# switch_matrix.net
KiCad netlist of a schematic drawn in Altium Designer
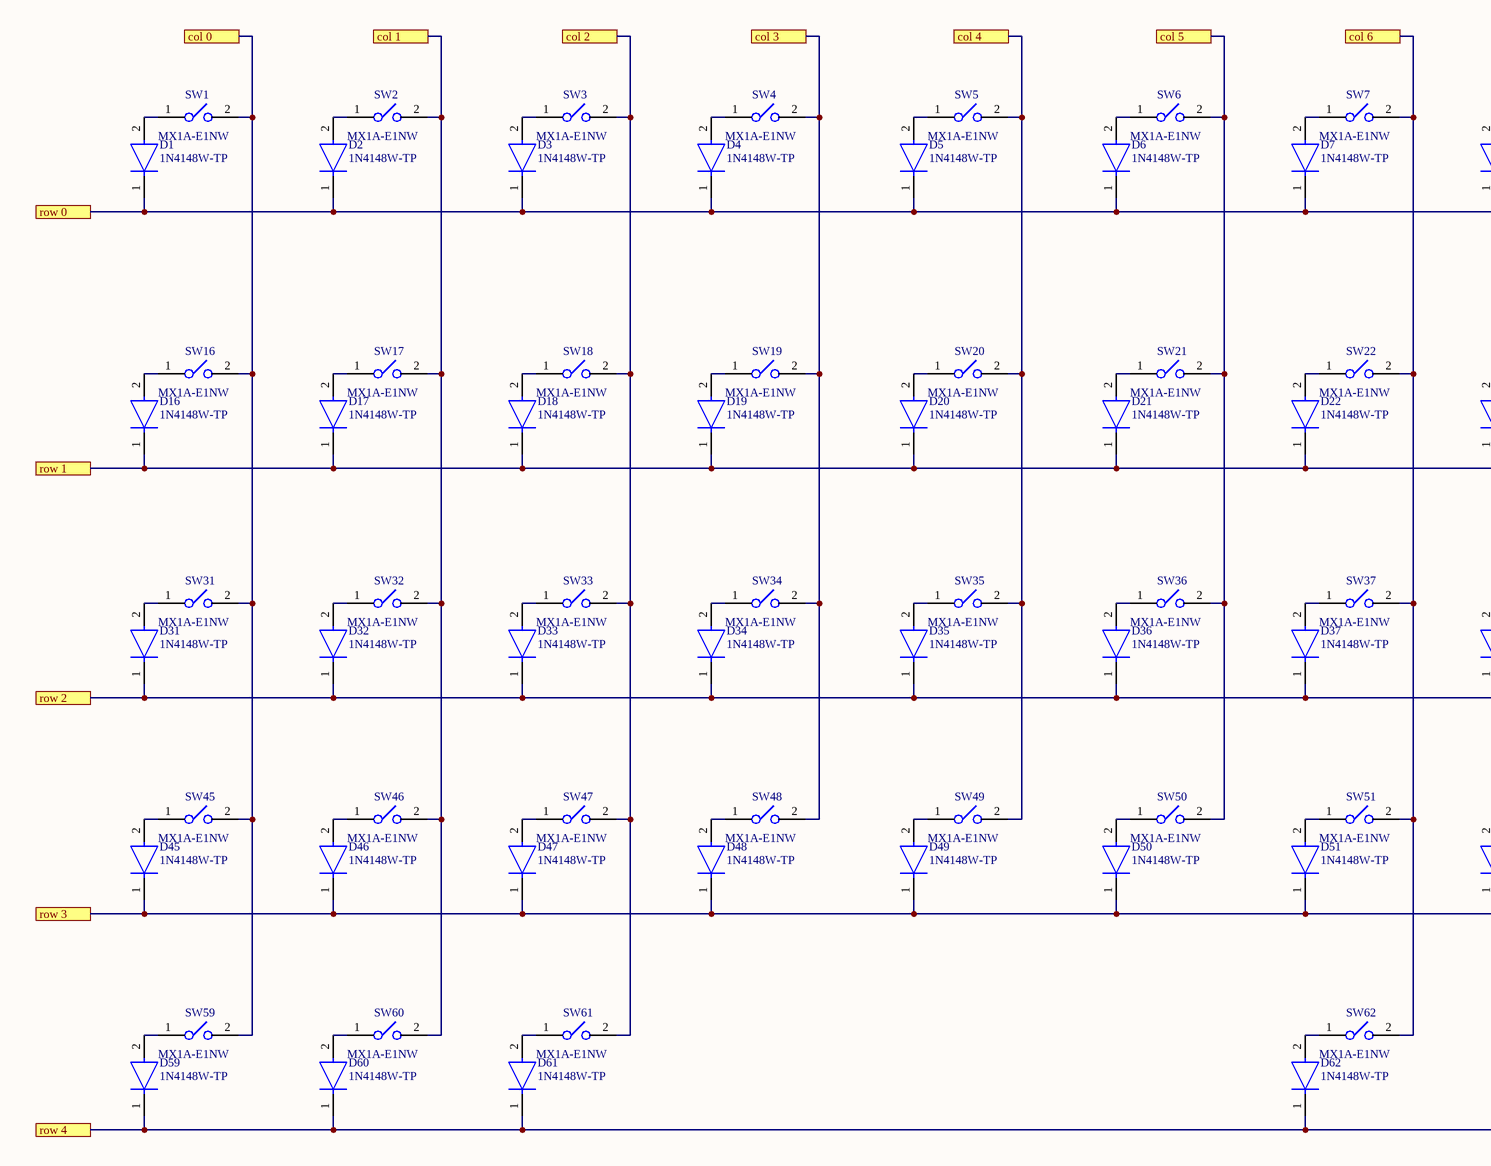
[diagram p0: switch matrix.SchDoc, left]
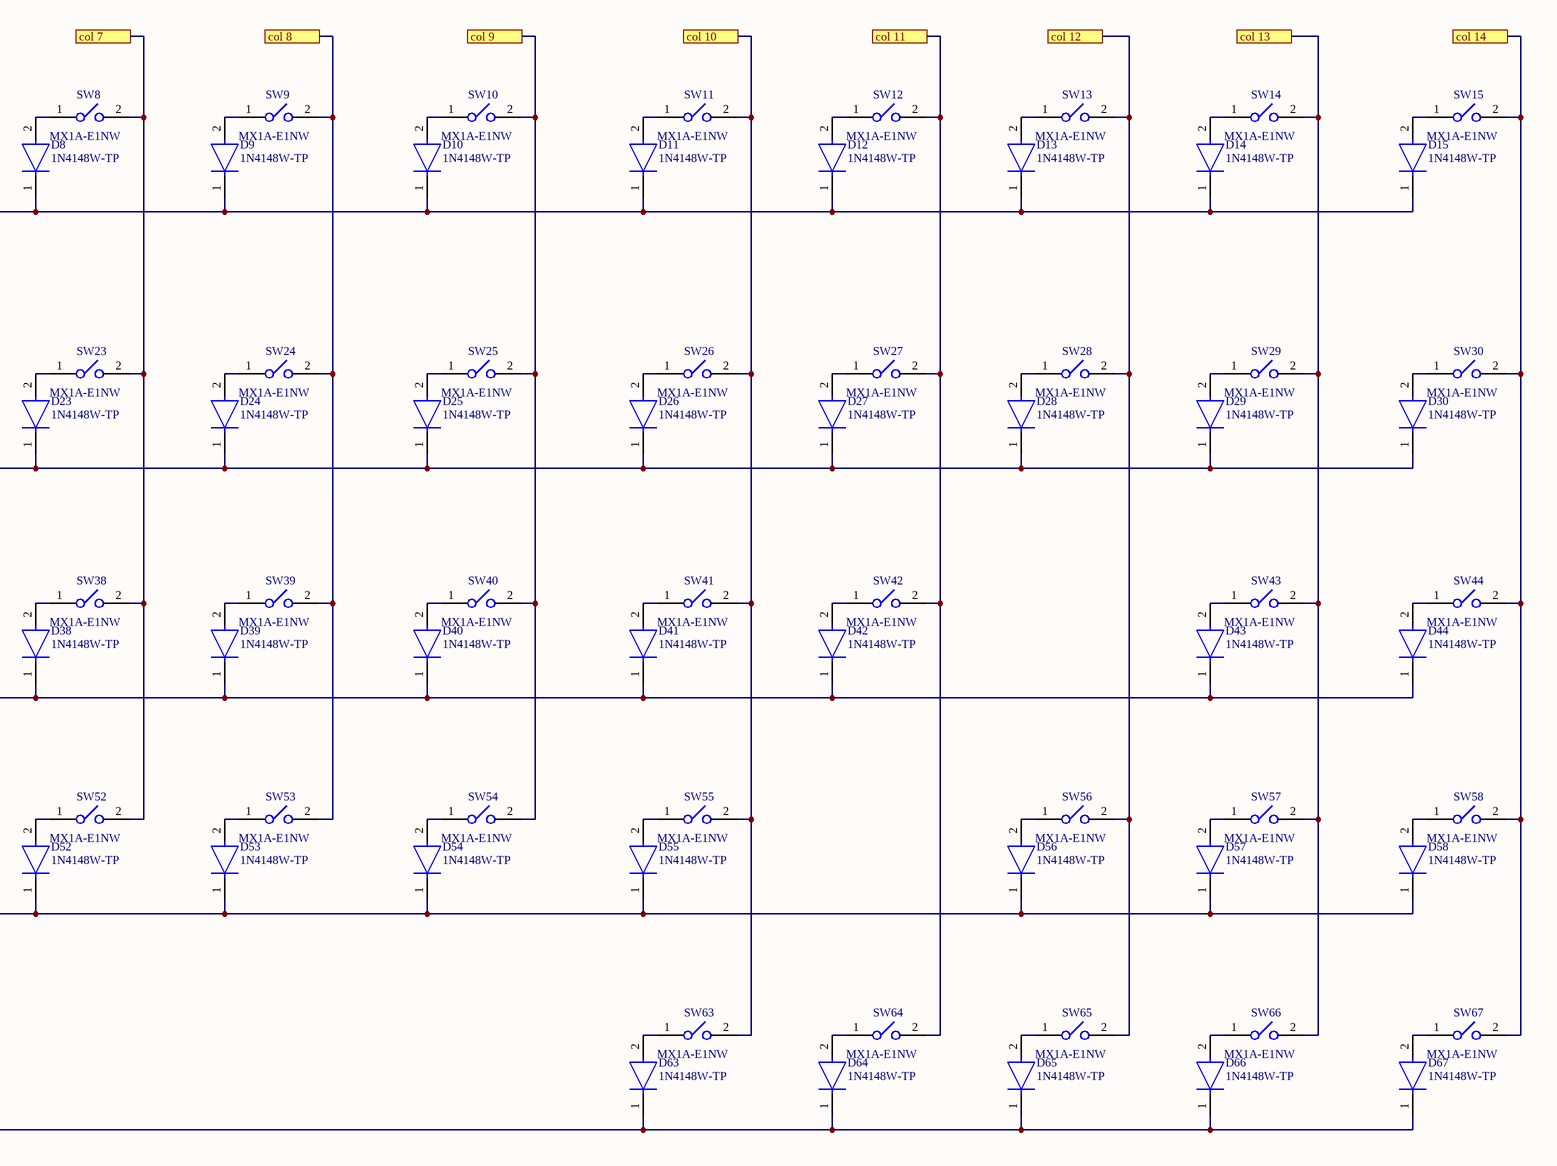
[diagram p1: switch matrix.SchDoc, right]

(export (version "E")
  (design (tool "Eeschema 10.0.6"))
  (components
    (comp (ref "D1")
      (value "1N4148W-TP")
      (footprint "FP-SOD-123-IPC_A")
      (description "DIODE GEN PURP 100V 150MA SOD123")
      (libsource (lib "Altium Content Vault") (part "d7152d700b627762746794eb795d46e"))
    )
    (comp (ref "D2")
      (value "1N4148W-TP")
      (footprint "FP-SOD-123-IPC_A")
      (description "DIODE GEN PURP 100V 150MA SOD123")
      (libsource (lib "Altium Content Vault") (part "d7152d700b627762746794eb795d46e"))
    )
    (comp (ref "D3")
      (value "1N4148W-TP")
      (footprint "FP-SOD-123-IPC_A")
      (description "DIODE GEN PURP 100V 150MA SOD123")
      (libsource (lib "Altium Content Vault") (part "d7152d700b627762746794eb795d46e"))
    )
    (comp (ref "D4")
      (value "1N4148W-TP")
      (footprint "FP-SOD-123-IPC_A")
      (description "DIODE GEN PURP 100V 150MA SOD123")
      (libsource (lib "Altium Content Vault") (part "d7152d700b627762746794eb795d46e"))
    )
    (comp (ref "D5")
      (value "1N4148W-TP")
      (footprint "FP-SOD-123-IPC_A")
      (description "DIODE GEN PURP 100V 150MA SOD123")
      (libsource (lib "Altium Content Vault") (part "d7152d700b627762746794eb795d46e"))
    )
    (comp (ref "D6")
      (value "1N4148W-TP")
      (footprint "FP-SOD-123-IPC_A")
      (description "DIODE GEN PURP 100V 150MA SOD123")
      (libsource (lib "Altium Content Vault") (part "d7152d700b627762746794eb795d46e"))
    )
    (comp (ref "D7")
      (value "1N4148W-TP")
      (footprint "FP-SOD-123-IPC_A")
      (description "DIODE GEN PURP 100V 150MA SOD123")
      (libsource (lib "Altium Content Vault") (part "d7152d700b627762746794eb795d46e"))
    )
    (comp (ref "D8")
      (value "1N4148W-TP")
      (footprint "FP-SOD-123-IPC_A")
      (description "DIODE GEN PURP 100V 150MA SOD123")
      (libsource (lib "Altium Content Vault") (part "d7152d700b627762746794eb795d46e"))
    )
    (comp (ref "D9")
      (value "1N4148W-TP")
      (footprint "FP-SOD-123-IPC_A")
      (description "DIODE GEN PURP 100V 150MA SOD123")
      (libsource (lib "Altium Content Vault") (part "d7152d700b627762746794eb795d46e"))
    )
    (comp (ref "D10")
      (value "1N4148W-TP")
      (footprint "FP-SOD-123-IPC_A")
      (description "DIODE GEN PURP 100V 150MA SOD123")
      (libsource (lib "Altium Content Vault") (part "d7152d700b627762746794eb795d46e"))
    )
    (comp (ref "D11")
      (value "1N4148W-TP")
      (footprint "FP-SOD-123-IPC_A")
      (description "DIODE GEN PURP 100V 150MA SOD123")
      (libsource (lib "Altium Content Vault") (part "d7152d700b627762746794eb795d46e"))
    )
    (comp (ref "D12")
      (value "1N4148W-TP")
      (footprint "FP-SOD-123-IPC_A")
      (description "DIODE GEN PURP 100V 150MA SOD123")
      (libsource (lib "Altium Content Vault") (part "d7152d700b627762746794eb795d46e"))
    )
    (comp (ref "D13")
      (value "1N4148W-TP")
      (footprint "FP-SOD-123-IPC_A")
      (description "DIODE GEN PURP 100V 150MA SOD123")
      (libsource (lib "Altium Content Vault") (part "d7152d700b627762746794eb795d46e"))
    )
    (comp (ref "D14")
      (value "1N4148W-TP")
      (footprint "FP-SOD-123-IPC_A")
      (description "DIODE GEN PURP 100V 150MA SOD123")
      (libsource (lib "Altium Content Vault") (part "d7152d700b627762746794eb795d46e"))
    )
    (comp (ref "D15")
      (value "1N4148W-TP")
      (footprint "FP-SOD-123-IPC_A")
      (description "DIODE GEN PURP 100V 150MA SOD123")
      (libsource (lib "Altium Content Vault") (part "d7152d700b627762746794eb795d46e"))
    )
    (comp (ref "D16")
      (value "1N4148W-TP")
      (footprint "FP-SOD-123-IPC_A")
      (description "DIODE GEN PURP 100V 150MA SOD123")
      (libsource (lib "Altium Content Vault") (part "d7152d700b627762746794eb795d46e"))
    )
    (comp (ref "D17")
      (value "1N4148W-TP")
      (footprint "FP-SOD-123-IPC_A")
      (description "DIODE GEN PURP 100V 150MA SOD123")
      (libsource (lib "Altium Content Vault") (part "d7152d700b627762746794eb795d46e"))
    )
    (comp (ref "D18")
      (value "1N4148W-TP")
      (footprint "FP-SOD-123-IPC_A")
      (description "DIODE GEN PURP 100V 150MA SOD123")
      (libsource (lib "Altium Content Vault") (part "d7152d700b627762746794eb795d46e"))
    )
    (comp (ref "D19")
      (value "1N4148W-TP")
      (footprint "FP-SOD-123-IPC_A")
      (description "DIODE GEN PURP 100V 150MA SOD123")
      (libsource (lib "Altium Content Vault") (part "d7152d700b627762746794eb795d46e"))
    )
    (comp (ref "D20")
      (value "1N4148W-TP")
      (footprint "FP-SOD-123-IPC_A")
      (description "DIODE GEN PURP 100V 150MA SOD123")
      (libsource (lib "Altium Content Vault") (part "d7152d700b627762746794eb795d46e"))
    )
    (comp (ref "D21")
      (value "1N4148W-TP")
      (footprint "FP-SOD-123-IPC_A")
      (description "DIODE GEN PURP 100V 150MA SOD123")
      (libsource (lib "Altium Content Vault") (part "d7152d700b627762746794eb795d46e"))
    )
    (comp (ref "D22")
      (value "1N4148W-TP")
      (footprint "FP-SOD-123-IPC_A")
      (description "DIODE GEN PURP 100V 150MA SOD123")
      (libsource (lib "Altium Content Vault") (part "d7152d700b627762746794eb795d46e"))
    )
    (comp (ref "D23")
      (value "1N4148W-TP")
      (footprint "FP-SOD-123-IPC_A")
      (description "DIODE GEN PURP 100V 150MA SOD123")
      (libsource (lib "Altium Content Vault") (part "d7152d700b627762746794eb795d46e"))
    )
    (comp (ref "D24")
      (value "1N4148W-TP")
      (footprint "FP-SOD-123-IPC_A")
      (description "DIODE GEN PURP 100V 150MA SOD123")
      (libsource (lib "Altium Content Vault") (part "d7152d700b627762746794eb795d46e"))
    )
    (comp (ref "D25")
      (value "1N4148W-TP")
      (footprint "FP-SOD-123-IPC_A")
      (description "DIODE GEN PURP 100V 150MA SOD123")
      (libsource (lib "Altium Content Vault") (part "d7152d700b627762746794eb795d46e"))
    )
    (comp (ref "D26")
      (value "1N4148W-TP")
      (footprint "FP-SOD-123-IPC_A")
      (description "DIODE GEN PURP 100V 150MA SOD123")
      (libsource (lib "Altium Content Vault") (part "d7152d700b627762746794eb795d46e"))
    )
    (comp (ref "D27")
      (value "1N4148W-TP")
      (footprint "FP-SOD-123-IPC_A")
      (description "DIODE GEN PURP 100V 150MA SOD123")
      (libsource (lib "Altium Content Vault") (part "d7152d700b627762746794eb795d46e"))
    )
    (comp (ref "D28")
      (value "1N4148W-TP")
      (footprint "FP-SOD-123-IPC_A")
      (description "DIODE GEN PURP 100V 150MA SOD123")
      (libsource (lib "Altium Content Vault") (part "d7152d700b627762746794eb795d46e"))
    )
    (comp (ref "D29")
      (value "1N4148W-TP")
      (footprint "FP-SOD-123-IPC_A")
      (description "DIODE GEN PURP 100V 150MA SOD123")
      (libsource (lib "Altium Content Vault") (part "d7152d700b627762746794eb795d46e"))
    )
    (comp (ref "D30")
      (value "1N4148W-TP")
      (footprint "FP-SOD-123-IPC_A")
      (description "DIODE GEN PURP 100V 150MA SOD123")
      (libsource (lib "Altium Content Vault") (part "d7152d700b627762746794eb795d46e"))
    )
    (comp (ref "D31")
      (value "1N4148W-TP")
      (footprint "FP-SOD-123-IPC_A")
      (description "DIODE GEN PURP 100V 150MA SOD123")
      (libsource (lib "Altium Content Vault") (part "d7152d700b627762746794eb795d46e"))
    )
    (comp (ref "D32")
      (value "1N4148W-TP")
      (footprint "FP-SOD-123-IPC_A")
      (description "DIODE GEN PURP 100V 150MA SOD123")
      (libsource (lib "Altium Content Vault") (part "d7152d700b627762746794eb795d46e"))
    )
    (comp (ref "D33")
      (value "1N4148W-TP")
      (footprint "FP-SOD-123-IPC_A")
      (description "DIODE GEN PURP 100V 150MA SOD123")
      (libsource (lib "Altium Content Vault") (part "d7152d700b627762746794eb795d46e"))
    )
    (comp (ref "D34")
      (value "1N4148W-TP")
      (footprint "FP-SOD-123-IPC_A")
      (description "DIODE GEN PURP 100V 150MA SOD123")
      (libsource (lib "Altium Content Vault") (part "d7152d700b627762746794eb795d46e"))
    )
    (comp (ref "D35")
      (value "1N4148W-TP")
      (footprint "FP-SOD-123-IPC_A")
      (description "DIODE GEN PURP 100V 150MA SOD123")
      (libsource (lib "Altium Content Vault") (part "d7152d700b627762746794eb795d46e"))
    )
    (comp (ref "D36")
      (value "1N4148W-TP")
      (footprint "FP-SOD-123-IPC_A")
      (description "DIODE GEN PURP 100V 150MA SOD123")
      (libsource (lib "Altium Content Vault") (part "d7152d700b627762746794eb795d46e"))
    )
    (comp (ref "D37")
      (value "1N4148W-TP")
      (footprint "FP-SOD-123-IPC_A")
      (description "DIODE GEN PURP 100V 150MA SOD123")
      (libsource (lib "Altium Content Vault") (part "d7152d700b627762746794eb795d46e"))
    )
    (comp (ref "D38")
      (value "1N4148W-TP")
      (footprint "FP-SOD-123-IPC_A")
      (description "DIODE GEN PURP 100V 150MA SOD123")
      (libsource (lib "Altium Content Vault") (part "d7152d700b627762746794eb795d46e"))
    )
    (comp (ref "D39")
      (value "1N4148W-TP")
      (footprint "FP-SOD-123-IPC_A")
      (description "DIODE GEN PURP 100V 150MA SOD123")
      (libsource (lib "Altium Content Vault") (part "d7152d700b627762746794eb795d46e"))
    )
    (comp (ref "D40")
      (value "1N4148W-TP")
      (footprint "FP-SOD-123-IPC_A")
      (description "DIODE GEN PURP 100V 150MA SOD123")
      (libsource (lib "Altium Content Vault") (part "d7152d700b627762746794eb795d46e"))
    )
    (comp (ref "D41")
      (value "1N4148W-TP")
      (footprint "FP-SOD-123-IPC_A")
      (description "DIODE GEN PURP 100V 150MA SOD123")
      (libsource (lib "Altium Content Vault") (part "d7152d700b627762746794eb795d46e"))
    )
    (comp (ref "D42")
      (value "1N4148W-TP")
      (footprint "FP-SOD-123-IPC_A")
      (description "DIODE GEN PURP 100V 150MA SOD123")
      (libsource (lib "Altium Content Vault") (part "d7152d700b627762746794eb795d46e"))
    )
    (comp (ref "D43")
      (value "1N4148W-TP")
      (footprint "FP-SOD-123-IPC_A")
      (description "DIODE GEN PURP 100V 150MA SOD123")
      (libsource (lib "Altium Content Vault") (part "d7152d700b627762746794eb795d46e"))
    )
    (comp (ref "D44")
      (value "1N4148W-TP")
      (footprint "FP-SOD-123-IPC_A")
      (description "DIODE GEN PURP 100V 150MA SOD123")
      (libsource (lib "Altium Content Vault") (part "d7152d700b627762746794eb795d46e"))
    )
    (comp (ref "D45")
      (value "1N4148W-TP")
      (footprint "FP-SOD-123-IPC_A")
      (description "DIODE GEN PURP 100V 150MA SOD123")
      (libsource (lib "Altium Content Vault") (part "d7152d700b627762746794eb795d46e"))
    )
    (comp (ref "D46")
      (value "1N4148W-TP")
      (footprint "FP-SOD-123-IPC_A")
      (description "DIODE GEN PURP 100V 150MA SOD123")
      (libsource (lib "Altium Content Vault") (part "d7152d700b627762746794eb795d46e"))
    )
    (comp (ref "D47")
      (value "1N4148W-TP")
      (footprint "FP-SOD-123-IPC_A")
      (description "DIODE GEN PURP 100V 150MA SOD123")
      (libsource (lib "Altium Content Vault") (part "d7152d700b627762746794eb795d46e"))
    )
    (comp (ref "D48")
      (value "1N4148W-TP")
      (footprint "FP-SOD-123-IPC_A")
      (description "DIODE GEN PURP 100V 150MA SOD123")
      (libsource (lib "Altium Content Vault") (part "d7152d700b627762746794eb795d46e"))
    )
    (comp (ref "D49")
      (value "1N4148W-TP")
      (footprint "FP-SOD-123-IPC_A")
      (description "DIODE GEN PURP 100V 150MA SOD123")
      (libsource (lib "Altium Content Vault") (part "d7152d700b627762746794eb795d46e"))
    )
    (comp (ref "D50")
      (value "1N4148W-TP")
      (footprint "FP-SOD-123-IPC_A")
      (description "DIODE GEN PURP 100V 150MA SOD123")
      (libsource (lib "Altium Content Vault") (part "d7152d700b627762746794eb795d46e"))
    )
    (comp (ref "D51")
      (value "1N4148W-TP")
      (footprint "FP-SOD-123-IPC_A")
      (description "DIODE GEN PURP 100V 150MA SOD123")
      (libsource (lib "Altium Content Vault") (part "d7152d700b627762746794eb795d46e"))
    )
    (comp (ref "D52")
      (value "1N4148W-TP")
      (footprint "FP-SOD-123-IPC_A")
      (description "DIODE GEN PURP 100V 150MA SOD123")
      (libsource (lib "Altium Content Vault") (part "d7152d700b627762746794eb795d46e"))
    )
    (comp (ref "D53")
      (value "1N4148W-TP")
      (footprint "FP-SOD-123-IPC_A")
      (description "DIODE GEN PURP 100V 150MA SOD123")
      (libsource (lib "Altium Content Vault") (part "d7152d700b627762746794eb795d46e"))
    )
    (comp (ref "D54")
      (value "1N4148W-TP")
      (footprint "FP-SOD-123-IPC_A")
      (description "DIODE GEN PURP 100V 150MA SOD123")
      (libsource (lib "Altium Content Vault") (part "d7152d700b627762746794eb795d46e"))
    )
    (comp (ref "D55")
      (value "1N4148W-TP")
      (footprint "FP-SOD-123-IPC_A")
      (description "DIODE GEN PURP 100V 150MA SOD123")
      (libsource (lib "Altium Content Vault") (part "d7152d700b627762746794eb795d46e"))
    )
    (comp (ref "D56")
      (value "1N4148W-TP")
      (footprint "FP-SOD-123-IPC_A")
      (description "DIODE GEN PURP 100V 150MA SOD123")
      (libsource (lib "Altium Content Vault") (part "d7152d700b627762746794eb795d46e"))
    )
    (comp (ref "D57")
      (value "1N4148W-TP")
      (footprint "FP-SOD-123-IPC_A")
      (description "DIODE GEN PURP 100V 150MA SOD123")
      (libsource (lib "Altium Content Vault") (part "d7152d700b627762746794eb795d46e"))
    )
    (comp (ref "D58")
      (value "1N4148W-TP")
      (footprint "FP-SOD-123-IPC_A")
      (description "DIODE GEN PURP 100V 150MA SOD123")
      (libsource (lib "Altium Content Vault") (part "d7152d700b627762746794eb795d46e"))
    )
    (comp (ref "D59")
      (value "1N4148W-TP")
      (footprint "FP-SOD-123-IPC_A")
      (description "DIODE GEN PURP 100V 150MA SOD123")
      (libsource (lib "Altium Content Vault") (part "d7152d700b627762746794eb795d46e"))
    )
    (comp (ref "D60")
      (value "1N4148W-TP")
      (footprint "FP-SOD-123-IPC_A")
      (description "DIODE GEN PURP 100V 150MA SOD123")
      (libsource (lib "Altium Content Vault") (part "d7152d700b627762746794eb795d46e"))
    )
    (comp (ref "D61")
      (value "1N4148W-TP")
      (footprint "FP-SOD-123-IPC_A")
      (description "DIODE GEN PURP 100V 150MA SOD123")
      (libsource (lib "Altium Content Vault") (part "d7152d700b627762746794eb795d46e"))
    )
    (comp (ref "D62")
      (value "1N4148W-TP")
      (footprint "FP-SOD-123-IPC_A")
      (description "DIODE GEN PURP 100V 150MA SOD123")
      (libsource (lib "Altium Content Vault") (part "d7152d700b627762746794eb795d46e"))
    )
    (comp (ref "D63")
      (value "1N4148W-TP")
      (footprint "FP-SOD-123-IPC_A")
      (description "DIODE GEN PURP 100V 150MA SOD123")
      (libsource (lib "Altium Content Vault") (part "d7152d700b627762746794eb795d46e"))
    )
    (comp (ref "D64")
      (value "1N4148W-TP")
      (footprint "FP-SOD-123-IPC_A")
      (description "DIODE GEN PURP 100V 150MA SOD123")
      (libsource (lib "Altium Content Vault") (part "d7152d700b627762746794eb795d46e"))
    )
    (comp (ref "D65")
      (value "1N4148W-TP")
      (footprint "FP-SOD-123-IPC_A")
      (description "DIODE GEN PURP 100V 150MA SOD123")
      (libsource (lib "Altium Content Vault") (part "d7152d700b627762746794eb795d46e"))
    )
    (comp (ref "D66")
      (value "1N4148W-TP")
      (footprint "FP-SOD-123-IPC_A")
      (description "DIODE GEN PURP 100V 150MA SOD123")
      (libsource (lib "Altium Content Vault") (part "d7152d700b627762746794eb795d46e"))
    )
    (comp (ref "D67")
      (value "1N4148W-TP")
      (footprint "FP-SOD-123-IPC_A")
      (description "DIODE GEN PURP 100V 150MA SOD123")
      (libsource (lib "Altium Content Vault") (part "d7152d700b627762746794eb795d46e"))
    )
    (comp (ref "SW1")
      (value "Switch_Key_Switch_MX1A-E1NW_eec")
      (footprint "SW_Cherry_MX_1.00u_PCB")
      (description "SWITCH PUSH SPST-NO 0.01A 12V")
      (fields
        (field (name "PART NUMBER") "MX1A-E1NW")
        (field (name "VOLTAGE") "12V")
        (field (name "MANUFACTURER") "Key Switch")
      )
      (libsource (lib "Switch_Key_Switch_MX1A-E1NW_eec") (part "Switch_Key_Switch_MX1A-E1NW_eec"))
    )
    (comp (ref "SW2")
      (value "Switch_Key_Switch_MX1A-E1NW_eec")
      (footprint "SW_Cherry_MX_1.00u_PCB")
      (description "SWITCH PUSH SPST-NO 0.01A 12V")
      (fields
        (field (name "PART NUMBER") "MX1A-E1NW")
        (field (name "VOLTAGE") "12V")
        (field (name "MANUFACTURER") "Key Switch")
      )
      (libsource (lib "Switch_Key_Switch_MX1A-E1NW_eec") (part "Switch_Key_Switch_MX1A-E1NW_eec"))
    )
    (comp (ref "SW3")
      (value "Switch_Key_Switch_MX1A-E1NW_eec")
      (footprint "SW_Cherry_MX_1.00u_PCB")
      (description "SWITCH PUSH SPST-NO 0.01A 12V")
      (fields
        (field (name "PART NUMBER") "MX1A-E1NW")
        (field (name "VOLTAGE") "12V")
        (field (name "MANUFACTURER") "Key Switch")
      )
      (libsource (lib "Switch_Key_Switch_MX1A-E1NW_eec") (part "Switch_Key_Switch_MX1A-E1NW_eec"))
    )
    (comp (ref "SW4")
      (value "Switch_Key_Switch_MX1A-E1NW_eec")
      (footprint "SW_Cherry_MX_1.00u_PCB")
      (description "SWITCH PUSH SPST-NO 0.01A 12V")
      (fields
        (field (name "PART NUMBER") "MX1A-E1NW")
        (field (name "VOLTAGE") "12V")
        (field (name "MANUFACTURER") "Key Switch")
      )
      (libsource (lib "Switch_Key_Switch_MX1A-E1NW_eec") (part "Switch_Key_Switch_MX1A-E1NW_eec"))
    )
    (comp (ref "SW5")
      (value "Switch_Key_Switch_MX1A-E1NW_eec")
      (footprint "SW_Cherry_MX_1.00u_PCB")
      (description "SWITCH PUSH SPST-NO 0.01A 12V")
      (fields
        (field (name "PART NUMBER") "MX1A-E1NW")
        (field (name "VOLTAGE") "12V")
        (field (name "MANUFACTURER") "Key Switch")
      )
      (libsource (lib "Switch_Key_Switch_MX1A-E1NW_eec") (part "Switch_Key_Switch_MX1A-E1NW_eec"))
    )
    (comp (ref "SW6")
      (value "Switch_Key_Switch_MX1A-E1NW_eec")
      (footprint "SW_Cherry_MX_1.00u_PCB")
      (description "SWITCH PUSH SPST-NO 0.01A 12V")
      (fields
        (field (name "PART NUMBER") "MX1A-E1NW")
        (field (name "VOLTAGE") "12V")
        (field (name "MANUFACTURER") "Key Switch")
      )
      (libsource (lib "Switch_Key_Switch_MX1A-E1NW_eec") (part "Switch_Key_Switch_MX1A-E1NW_eec"))
    )
    (comp (ref "SW7")
      (value "Switch_Key_Switch_MX1A-E1NW_eec")
      (footprint "SW_Cherry_MX_1.00u_PCB")
      (description "SWITCH PUSH SPST-NO 0.01A 12V")
      (fields
        (field (name "PART NUMBER") "MX1A-E1NW")
        (field (name "VOLTAGE") "12V")
        (field (name "MANUFACTURER") "Key Switch")
      )
      (libsource (lib "Switch_Key_Switch_MX1A-E1NW_eec") (part "Switch_Key_Switch_MX1A-E1NW_eec"))
    )
    (comp (ref "SW8")
      (value "Switch_Key_Switch_MX1A-E1NW_eec")
      (footprint "SW_Cherry_MX_1.00u_PCB")
      (description "SWITCH PUSH SPST-NO 0.01A 12V")
      (fields
        (field (name "PART NUMBER") "MX1A-E1NW")
        (field (name "VOLTAGE") "12V")
        (field (name "MANUFACTURER") "Key Switch")
      )
      (libsource (lib "Switch_Key_Switch_MX1A-E1NW_eec") (part "Switch_Key_Switch_MX1A-E1NW_eec"))
    )
    (comp (ref "SW9")
      (value "Switch_Key_Switch_MX1A-E1NW_eec")
      (footprint "SW_Cherry_MX_1.00u_PCB")
      (description "SWITCH PUSH SPST-NO 0.01A 12V")
      (fields
        (field (name "PART NUMBER") "MX1A-E1NW")
        (field (name "VOLTAGE") "12V")
        (field (name "MANUFACTURER") "Key Switch")
      )
      (libsource (lib "Switch_Key_Switch_MX1A-E1NW_eec") (part "Switch_Key_Switch_MX1A-E1NW_eec"))
    )
    (comp (ref "SW10")
      (value "Switch_Key_Switch_MX1A-E1NW_eec")
      (footprint "SW_Cherry_MX_1.00u_PCB")
      (description "SWITCH PUSH SPST-NO 0.01A 12V")
      (fields
        (field (name "PART NUMBER") "MX1A-E1NW")
        (field (name "VOLTAGE") "12V")
        (field (name "MANUFACTURER") "Key Switch")
      )
      (libsource (lib "Switch_Key_Switch_MX1A-E1NW_eec") (part "Switch_Key_Switch_MX1A-E1NW_eec"))
    )
    (comp (ref "SW11")
      (value "Switch_Key_Switch_MX1A-E1NW_eec")
      (footprint "SW_Cherry_MX_1.00u_PCB")
      (description "SWITCH PUSH SPST-NO 0.01A 12V")
      (fields
        (field (name "PART NUMBER") "MX1A-E1NW")
        (field (name "VOLTAGE") "12V")
        (field (name "MANUFACTURER") "Key Switch")
      )
      (libsource (lib "Switch_Key_Switch_MX1A-E1NW_eec") (part "Switch_Key_Switch_MX1A-E1NW_eec"))
    )
    (comp (ref "SW12")
      (value "Switch_Key_Switch_MX1A-E1NW_eec")
      (footprint "SW_Cherry_MX_1.00u_PCB")
      (description "SWITCH PUSH SPST-NO 0.01A 12V")
      (fields
        (field (name "PART NUMBER") "MX1A-E1NW")
        (field (name "VOLTAGE") "12V")
        (field (name "MANUFACTURER") "Key Switch")
      )
      (libsource (lib "Switch_Key_Switch_MX1A-E1NW_eec") (part "Switch_Key_Switch_MX1A-E1NW_eec"))
    )
    (comp (ref "SW13")
      (value "Switch_Key_Switch_MX1A-E1NW_eec")
      (footprint "SW_Cherry_MX_1.00u_PCB")
      (description "SWITCH PUSH SPST-NO 0.01A 12V")
      (fields
        (field (name "PART NUMBER") "MX1A-E1NW")
        (field (name "VOLTAGE") "12V")
        (field (name "MANUFACTURER") "Key Switch")
      )
      (libsource (lib "Switch_Key_Switch_MX1A-E1NW_eec") (part "Switch_Key_Switch_MX1A-E1NW_eec"))
    )
    (comp (ref "SW14")
      (value "Switch_Key_Switch_MX1A-E1NW_eec")
      (footprint "SW_Cherry_MX_2.00u_PCB")
      (description "SWITCH PUSH SPST-NO 0.01A 12V")
      (fields
        (field (name "PART NUMBER") "MX1A-E1NW")
        (field (name "VOLTAGE") "12V")
        (field (name "MANUFACTURER") "Key Switch")
      )
      (libsource (lib "Switch_Key_Switch_MX1A-E1NW_eec") (part "Switch_Key_Switch_MX1A-E1NW_eec"))
    )
    (comp (ref "SW15")
      (value "Switch_Key_Switch_MX1A-E1NW_eec")
      (footprint "SW_Cherry_MX_1.00u_PCB")
      (description "SWITCH PUSH SPST-NO 0.01A 12V")
      (fields
        (field (name "PART NUMBER") "MX1A-E1NW")
        (field (name "VOLTAGE") "12V")
        (field (name "MANUFACTURER") "Key Switch")
      )
      (libsource (lib "Switch_Key_Switch_MX1A-E1NW_eec") (part "Switch_Key_Switch_MX1A-E1NW_eec"))
    )
    (comp (ref "SW16")
      (value "Switch_Key_Switch_MX1A-E1NW_eec")
      (footprint "SW_Cherry_MX_1.50u_PCB")
      (description "SWITCH PUSH SPST-NO 0.01A 12V")
      (fields
        (field (name "PART NUMBER") "MX1A-E1NW")
        (field (name "VOLTAGE") "12V")
        (field (name "MANUFACTURER") "Key Switch")
      )
      (libsource (lib "Switch_Key_Switch_MX1A-E1NW_eec") (part "Switch_Key_Switch_MX1A-E1NW_eec"))
    )
    (comp (ref "SW17")
      (value "Switch_Key_Switch_MX1A-E1NW_eec")
      (footprint "SW_Cherry_MX_1.00u_PCB")
      (description "SWITCH PUSH SPST-NO 0.01A 12V")
      (fields
        (field (name "PART NUMBER") "MX1A-E1NW")
        (field (name "VOLTAGE") "12V")
        (field (name "MANUFACTURER") "Key Switch")
      )
      (libsource (lib "Switch_Key_Switch_MX1A-E1NW_eec") (part "Switch_Key_Switch_MX1A-E1NW_eec"))
    )
    (comp (ref "SW18")
      (value "Switch_Key_Switch_MX1A-E1NW_eec")
      (footprint "SW_Cherry_MX_1.00u_PCB")
      (description "SWITCH PUSH SPST-NO 0.01A 12V")
      (fields
        (field (name "PART NUMBER") "MX1A-E1NW")
        (field (name "VOLTAGE") "12V")
        (field (name "MANUFACTURER") "Key Switch")
      )
      (libsource (lib "Switch_Key_Switch_MX1A-E1NW_eec") (part "Switch_Key_Switch_MX1A-E1NW_eec"))
    )
    (comp (ref "SW19")
      (value "Switch_Key_Switch_MX1A-E1NW_eec")
      (footprint "SW_Cherry_MX_1.00u_PCB")
      (description "SWITCH PUSH SPST-NO 0.01A 12V")
      (fields
        (field (name "PART NUMBER") "MX1A-E1NW")
        (field (name "VOLTAGE") "12V")
        (field (name "MANUFACTURER") "Key Switch")
      )
      (libsource (lib "Switch_Key_Switch_MX1A-E1NW_eec") (part "Switch_Key_Switch_MX1A-E1NW_eec"))
    )
    (comp (ref "SW20")
      (value "Switch_Key_Switch_MX1A-E1NW_eec")
      (footprint "SW_Cherry_MX_1.00u_PCB")
      (description "SWITCH PUSH SPST-NO 0.01A 12V")
      (fields
        (field (name "PART NUMBER") "MX1A-E1NW")
        (field (name "VOLTAGE") "12V")
        (field (name "MANUFACTURER") "Key Switch")
      )
      (libsource (lib "Switch_Key_Switch_MX1A-E1NW_eec") (part "Switch_Key_Switch_MX1A-E1NW_eec"))
    )
    (comp (ref "SW21")
      (value "Switch_Key_Switch_MX1A-E1NW_eec")
      (footprint "SW_Cherry_MX_1.00u_PCB")
      (description "SWITCH PUSH SPST-NO 0.01A 12V")
      (fields
        (field (name "PART NUMBER") "MX1A-E1NW")
        (field (name "VOLTAGE") "12V")
        (field (name "MANUFACTURER") "Key Switch")
      )
      (libsource (lib "Switch_Key_Switch_MX1A-E1NW_eec") (part "Switch_Key_Switch_MX1A-E1NW_eec"))
    )
    (comp (ref "SW22")
      (value "Switch_Key_Switch_MX1A-E1NW_eec")
      (footprint "SW_Cherry_MX_1.00u_PCB")
      (description "SWITCH PUSH SPST-NO 0.01A 12V")
      (fields
        (field (name "PART NUMBER") "MX1A-E1NW")
        (field (name "VOLTAGE") "12V")
        (field (name "MANUFACTURER") "Key Switch")
      )
      (libsource (lib "Switch_Key_Switch_MX1A-E1NW_eec") (part "Switch_Key_Switch_MX1A-E1NW_eec"))
    )
    (comp (ref "SW23")
      (value "Switch_Key_Switch_MX1A-E1NW_eec")
      (footprint "SW_Cherry_MX_1.00u_PCB")
      (description "SWITCH PUSH SPST-NO 0.01A 12V")
      (fields
        (field (name "PART NUMBER") "MX1A-E1NW")
        (field (name "VOLTAGE") "12V")
        (field (name "MANUFACTURER") "Key Switch")
      )
      (libsource (lib "Switch_Key_Switch_MX1A-E1NW_eec") (part "Switch_Key_Switch_MX1A-E1NW_eec"))
    )
    (comp (ref "SW24")
      (value "Switch_Key_Switch_MX1A-E1NW_eec")
      (footprint "SW_Cherry_MX_1.00u_PCB")
      (description "SWITCH PUSH SPST-NO 0.01A 12V")
      (fields
        (field (name "PART NUMBER") "MX1A-E1NW")
        (field (name "VOLTAGE") "12V")
        (field (name "MANUFACTURER") "Key Switch")
      )
      (libsource (lib "Switch_Key_Switch_MX1A-E1NW_eec") (part "Switch_Key_Switch_MX1A-E1NW_eec"))
    )
    (comp (ref "SW25")
      (value "Switch_Key_Switch_MX1A-E1NW_eec")
      (footprint "SW_Cherry_MX_1.00u_PCB")
      (description "SWITCH PUSH SPST-NO 0.01A 12V")
      (fields
        (field (name "PART NUMBER") "MX1A-E1NW")
        (field (name "VOLTAGE") "12V")
        (field (name "MANUFACTURER") "Key Switch")
      )
      (libsource (lib "Switch_Key_Switch_MX1A-E1NW_eec") (part "Switch_Key_Switch_MX1A-E1NW_eec"))
    )
    (comp (ref "SW26")
      (value "Switch_Key_Switch_MX1A-E1NW_eec")
      (footprint "SW_Cherry_MX_1.00u_PCB")
      (description "SWITCH PUSH SPST-NO 0.01A 12V")
      (fields
        (field (name "PART NUMBER") "MX1A-E1NW")
        (field (name "VOLTAGE") "12V")
        (field (name "MANUFACTURER") "Key Switch")
      )
      (libsource (lib "Switch_Key_Switch_MX1A-E1NW_eec") (part "Switch_Key_Switch_MX1A-E1NW_eec"))
    )
    (comp (ref "SW27")
      (value "Switch_Key_Switch_MX1A-E1NW_eec")
      (footprint "SW_Cherry_MX_1.00u_PCB")
      (description "SWITCH PUSH SPST-NO 0.01A 12V")
      (fields
        (field (name "PART NUMBER") "MX1A-E1NW")
        (field (name "VOLTAGE") "12V")
        (field (name "MANUFACTURER") "Key Switch")
      )
      (libsource (lib "Switch_Key_Switch_MX1A-E1NW_eec") (part "Switch_Key_Switch_MX1A-E1NW_eec"))
    )
    (comp (ref "SW28")
      (value "Switch_Key_Switch_MX1A-E1NW_eec")
      (footprint "SW_Cherry_MX_1.00u_PCB")
      (description "SWITCH PUSH SPST-NO 0.01A 12V")
      (fields
        (field (name "PART NUMBER") "MX1A-E1NW")
        (field (name "VOLTAGE") "12V")
        (field (name "MANUFACTURER") "Key Switch")
      )
      (libsource (lib "Switch_Key_Switch_MX1A-E1NW_eec") (part "Switch_Key_Switch_MX1A-E1NW_eec"))
    )
    (comp (ref "SW29")
      (value "Switch_Key_Switch_MX1A-E1NW_eec")
      (footprint "SW_Cherry_MX_1.50u_PCB")
      (description "SWITCH PUSH SPST-NO 0.01A 12V")
      (fields
        (field (name "PART NUMBER") "MX1A-E1NW")
        (field (name "VOLTAGE") "12V")
        (field (name "MANUFACTURER") "Key Switch")
      )
      (libsource (lib "Switch_Key_Switch_MX1A-E1NW_eec") (part "Switch_Key_Switch_MX1A-E1NW_eec"))
    )
    (comp (ref "SW30")
      (value "Switch_Key_Switch_MX1A-E1NW_eec")
      (footprint "SW_Cherry_MX_1.00u_PCB")
      (description "SWITCH PUSH SPST-NO 0.01A 12V")
      (fields
        (field (name "PART NUMBER") "MX1A-E1NW")
        (field (name "VOLTAGE") "12V")
        (field (name "MANUFACTURER") "Key Switch")
      )
      (libsource (lib "Switch_Key_Switch_MX1A-E1NW_eec") (part "Switch_Key_Switch_MX1A-E1NW_eec"))
    )
    (comp (ref "SW31")
      (value "Switch_Key_Switch_MX1A-E1NW_eec")
      (footprint "SW_Cherry_MX_1.75u_PCB")
      (description "SWITCH PUSH SPST-NO 0.01A 12V")
      (fields
        (field (name "PART NUMBER") "MX1A-E1NW")
        (field (name "VOLTAGE") "12V")
        (field (name "MANUFACTURER") "Key Switch")
      )
      (libsource (lib "Switch_Key_Switch_MX1A-E1NW_eec") (part "Switch_Key_Switch_MX1A-E1NW_eec"))
    )
    (comp (ref "SW32")
      (value "Switch_Key_Switch_MX1A-E1NW_eec")
      (footprint "SW_Cherry_MX_1.00u_PCB")
      (description "SWITCH PUSH SPST-NO 0.01A 12V")
      (fields
        (field (name "PART NUMBER") "MX1A-E1NW")
        (field (name "VOLTAGE") "12V")
        (field (name "MANUFACTURER") "Key Switch")
      )
      (libsource (lib "Switch_Key_Switch_MX1A-E1NW_eec") (part "Switch_Key_Switch_MX1A-E1NW_eec"))
    )
    (comp (ref "SW33")
      (value "Switch_Key_Switch_MX1A-E1NW_eec")
      (footprint "SW_Cherry_MX_1.00u_PCB")
      (description "SWITCH PUSH SPST-NO 0.01A 12V")
      (fields
        (field (name "PART NUMBER") "MX1A-E1NW")
        (field (name "VOLTAGE") "12V")
        (field (name "MANUFACTURER") "Key Switch")
      )
      (libsource (lib "Switch_Key_Switch_MX1A-E1NW_eec") (part "Switch_Key_Switch_MX1A-E1NW_eec"))
    )
    (comp (ref "SW34")
      (value "Switch_Key_Switch_MX1A-E1NW_eec")
      (footprint "SW_Cherry_MX_1.00u_PCB")
      (description "SWITCH PUSH SPST-NO 0.01A 12V")
      (fields
        (field (name "PART NUMBER") "MX1A-E1NW")
        (field (name "VOLTAGE") "12V")
        (field (name "MANUFACTURER") "Key Switch")
      )
      (libsource (lib "Switch_Key_Switch_MX1A-E1NW_eec") (part "Switch_Key_Switch_MX1A-E1NW_eec"))
    )
    (comp (ref "SW35")
      (value "Switch_Key_Switch_MX1A-E1NW_eec")
      (footprint "SW_Cherry_MX_1.00u_PCB")
      (description "SWITCH PUSH SPST-NO 0.01A 12V")
      (fields
        (field (name "PART NUMBER") "MX1A-E1NW")
        (field (name "VOLTAGE") "12V")
        (field (name "MANUFACTURER") "Key Switch")
      )
      (libsource (lib "Switch_Key_Switch_MX1A-E1NW_eec") (part "Switch_Key_Switch_MX1A-E1NW_eec"))
    )
    (comp (ref "SW36")
      (value "Switch_Key_Switch_MX1A-E1NW_eec")
      (footprint "SW_Cherry_MX_1.00u_PCB")
      (description "SWITCH PUSH SPST-NO 0.01A 12V")
      (fields
        (field (name "PART NUMBER") "MX1A-E1NW")
        (field (name "VOLTAGE") "12V")
        (field (name "MANUFACTURER") "Key Switch")
      )
      (libsource (lib "Switch_Key_Switch_MX1A-E1NW_eec") (part "Switch_Key_Switch_MX1A-E1NW_eec"))
    )
    (comp (ref "SW37")
      (value "Switch_Key_Switch_MX1A-E1NW_eec")
      (footprint "SW_Cherry_MX_1.00u_PCB")
      (description "SWITCH PUSH SPST-NO 0.01A 12V")
      (fields
        (field (name "PART NUMBER") "MX1A-E1NW")
        (field (name "VOLTAGE") "12V")
        (field (name "MANUFACTURER") "Key Switch")
      )
      (libsource (lib "Switch_Key_Switch_MX1A-E1NW_eec") (part "Switch_Key_Switch_MX1A-E1NW_eec"))
    )
    (comp (ref "SW38")
      (value "Switch_Key_Switch_MX1A-E1NW_eec")
      (footprint "SW_Cherry_MX_1.00u_PCB")
      (description "SWITCH PUSH SPST-NO 0.01A 12V")
      (fields
        (field (name "PART NUMBER") "MX1A-E1NW")
        (field (name "VOLTAGE") "12V")
        (field (name "MANUFACTURER") "Key Switch")
      )
      (libsource (lib "Switch_Key_Switch_MX1A-E1NW_eec") (part "Switch_Key_Switch_MX1A-E1NW_eec"))
    )
    (comp (ref "SW39")
      (value "Switch_Key_Switch_MX1A-E1NW_eec")
      (footprint "SW_Cherry_MX_1.00u_PCB")
      (description "SWITCH PUSH SPST-NO 0.01A 12V")
      (fields
        (field (name "PART NUMBER") "MX1A-E1NW")
        (field (name "VOLTAGE") "12V")
        (field (name "MANUFACTURER") "Key Switch")
      )
      (libsource (lib "Switch_Key_Switch_MX1A-E1NW_eec") (part "Switch_Key_Switch_MX1A-E1NW_eec"))
    )
    (comp (ref "SW40")
      (value "Switch_Key_Switch_MX1A-E1NW_eec")
      (footprint "SW_Cherry_MX_1.00u_PCB")
      (description "SWITCH PUSH SPST-NO 0.01A 12V")
      (fields
        (field (name "PART NUMBER") "MX1A-E1NW")
        (field (name "VOLTAGE") "12V")
        (field (name "MANUFACTURER") "Key Switch")
      )
      (libsource (lib "Switch_Key_Switch_MX1A-E1NW_eec") (part "Switch_Key_Switch_MX1A-E1NW_eec"))
    )
    (comp (ref "SW41")
      (value "Switch_Key_Switch_MX1A-E1NW_eec")
      (footprint "SW_Cherry_MX_1.00u_PCB")
      (description "SWITCH PUSH SPST-NO 0.01A 12V")
      (fields
        (field (name "PART NUMBER") "MX1A-E1NW")
        (field (name "VOLTAGE") "12V")
        (field (name "MANUFACTURER") "Key Switch")
      )
      (libsource (lib "Switch_Key_Switch_MX1A-E1NW_eec") (part "Switch_Key_Switch_MX1A-E1NW_eec"))
    )
    (comp (ref "SW42")
      (value "Switch_Key_Switch_MX1A-E1NW_eec")
      (footprint "SW_Cherry_MX_1.00u_PCB")
      (description "SWITCH PUSH SPST-NO 0.01A 12V")
      (fields
        (field (name "PART NUMBER") "MX1A-E1NW")
        (field (name "VOLTAGE") "12V")
        (field (name "MANUFACTURER") "Key Switch")
      )
      (libsource (lib "Switch_Key_Switch_MX1A-E1NW_eec") (part "Switch_Key_Switch_MX1A-E1NW_eec"))
    )
    (comp (ref "SW43")
      (value "Switch_Key_Switch_MX1A-E1NW_eec")
      (footprint "SW_Cherry_MX_2.00u_PCB")
      (description "SWITCH PUSH SPST-NO 0.01A 12V")
      (fields
        (field (name "PART NUMBER") "MX1A-E1NW")
        (field (name "VOLTAGE") "12V")
        (field (name "MANUFACTURER") "Key Switch")
      )
      (libsource (lib "Switch_Key_Switch_MX1A-E1NW_eec") (part "Switch_Key_Switch_MX1A-E1NW_eec"))
    )
    (comp (ref "SW44")
      (value "Switch_Key_Switch_MX1A-E1NW_eec")
      (footprint "SW_Cherry_MX_1.00u_PCB")
      (description "SWITCH PUSH SPST-NO 0.01A 12V")
      (fields
        (field (name "PART NUMBER") "MX1A-E1NW")
        (field (name "VOLTAGE") "12V")
        (field (name "MANUFACTURER") "Key Switch")
      )
      (libsource (lib "Switch_Key_Switch_MX1A-E1NW_eec") (part "Switch_Key_Switch_MX1A-E1NW_eec"))
    )
    (comp (ref "SW45")
      (value "Switch_Key_Switch_MX1A-E1NW_eec")
      (footprint "SW_Cherry_MX_2.00u_PCB")
      (description "SWITCH PUSH SPST-NO 0.01A 12V")
      (fields
        (field (name "PART NUMBER") "MX1A-E1NW")
        (field (name "VOLTAGE") "12V")
        (field (name "MANUFACTURER") "Key Switch")
      )
      (libsource (lib "Switch_Key_Switch_MX1A-E1NW_eec") (part "Switch_Key_Switch_MX1A-E1NW_eec"))
    )
    (comp (ref "SW46")
      (value "Switch_Key_Switch_MX1A-E1NW_eec")
      (footprint "SW_Cherry_MX_1.00u_PCB")
      (description "SWITCH PUSH SPST-NO 0.01A 12V")
      (fields
        (field (name "PART NUMBER") "MX1A-E1NW")
        (field (name "VOLTAGE") "12V")
        (field (name "MANUFACTURER") "Key Switch")
      )
      (libsource (lib "Switch_Key_Switch_MX1A-E1NW_eec") (part "Switch_Key_Switch_MX1A-E1NW_eec"))
    )
    (comp (ref "SW47")
      (value "Switch_Key_Switch_MX1A-E1NW_eec")
      (footprint "SW_Cherry_MX_1.00u_PCB")
      (description "SWITCH PUSH SPST-NO 0.01A 12V")
      (fields
        (field (name "PART NUMBER") "MX1A-E1NW")
        (field (name "VOLTAGE") "12V")
        (field (name "MANUFACTURER") "Key Switch")
      )
      (libsource (lib "Switch_Key_Switch_MX1A-E1NW_eec") (part "Switch_Key_Switch_MX1A-E1NW_eec"))
    )
    (comp (ref "SW48")
      (value "Switch_Key_Switch_MX1A-E1NW_eec")
      (footprint "SW_Cherry_MX_1.00u_PCB")
      (description "SWITCH PUSH SPST-NO 0.01A 12V")
      (fields
        (field (name "PART NUMBER") "MX1A-E1NW")
        (field (name "VOLTAGE") "12V")
        (field (name "MANUFACTURER") "Key Switch")
      )
      (libsource (lib "Switch_Key_Switch_MX1A-E1NW_eec") (part "Switch_Key_Switch_MX1A-E1NW_eec"))
    )
    (comp (ref "SW49")
      (value "Switch_Key_Switch_MX1A-E1NW_eec")
      (footprint "SW_Cherry_MX_1.00u_PCB")
      (description "SWITCH PUSH SPST-NO 0.01A 12V")
      (fields
        (field (name "PART NUMBER") "MX1A-E1NW")
        (field (name "VOLTAGE") "12V")
        (field (name "MANUFACTURER") "Key Switch")
      )
      (libsource (lib "Switch_Key_Switch_MX1A-E1NW_eec") (part "Switch_Key_Switch_MX1A-E1NW_eec"))
    )
    (comp (ref "SW50")
      (value "Switch_Key_Switch_MX1A-E1NW_eec")
      (footprint "SW_Cherry_MX_1.00u_PCB")
      (description "SWITCH PUSH SPST-NO 0.01A 12V")
      (fields
        (field (name "PART NUMBER") "MX1A-E1NW")
        (field (name "VOLTAGE") "12V")
        (field (name "MANUFACTURER") "Key Switch")
      )
      (libsource (lib "Switch_Key_Switch_MX1A-E1NW_eec") (part "Switch_Key_Switch_MX1A-E1NW_eec"))
    )
    (comp (ref "SW51")
      (value "Switch_Key_Switch_MX1A-E1NW_eec")
      (footprint "SW_Cherry_MX_1.00u_PCB")
      (description "SWITCH PUSH SPST-NO 0.01A 12V")
      (fields
        (field (name "PART NUMBER") "MX1A-E1NW")
        (field (name "VOLTAGE") "12V")
        (field (name "MANUFACTURER") "Key Switch")
      )
      (libsource (lib "Switch_Key_Switch_MX1A-E1NW_eec") (part "Switch_Key_Switch_MX1A-E1NW_eec"))
    )
    (comp (ref "SW52")
      (value "Switch_Key_Switch_MX1A-E1NW_eec")
      (footprint "SW_Cherry_MX_1.00u_PCB")
      (description "SWITCH PUSH SPST-NO 0.01A 12V")
      (fields
        (field (name "PART NUMBER") "MX1A-E1NW")
        (field (name "VOLTAGE") "12V")
        (field (name "MANUFACTURER") "Key Switch")
      )
      (libsource (lib "Switch_Key_Switch_MX1A-E1NW_eec") (part "Switch_Key_Switch_MX1A-E1NW_eec"))
    )
    (comp (ref "SW53")
      (value "Switch_Key_Switch_MX1A-E1NW_eec")
      (footprint "SW_Cherry_MX_1.00u_PCB")
      (description "SWITCH PUSH SPST-NO 0.01A 12V")
      (fields
        (field (name "PART NUMBER") "MX1A-E1NW")
        (field (name "VOLTAGE") "12V")
        (field (name "MANUFACTURER") "Key Switch")
      )
      (libsource (lib "Switch_Key_Switch_MX1A-E1NW_eec") (part "Switch_Key_Switch_MX1A-E1NW_eec"))
    )
    (comp (ref "SW54")
      (value "Switch_Key_Switch_MX1A-E1NW_eec")
      (footprint "SW_Cherry_MX_1.00u_PCB")
      (description "SWITCH PUSH SPST-NO 0.01A 12V")
      (fields
        (field (name "PART NUMBER") "MX1A-E1NW")
        (field (name "VOLTAGE") "12V")
        (field (name "MANUFACTURER") "Key Switch")
      )
      (libsource (lib "Switch_Key_Switch_MX1A-E1NW_eec") (part "Switch_Key_Switch_MX1A-E1NW_eec"))
    )
    (comp (ref "SW55")
      (value "Switch_Key_Switch_MX1A-E1NW_eec")
      (footprint "SW_Cherry_MX_1.00u_PCB")
      (description "SWITCH PUSH SPST-NO 0.01A 12V")
      (fields
        (field (name "PART NUMBER") "MX1A-E1NW")
        (field (name "VOLTAGE") "12V")
        (field (name "MANUFACTURER") "Key Switch")
      )
      (libsource (lib "Switch_Key_Switch_MX1A-E1NW_eec") (part "Switch_Key_Switch_MX1A-E1NW_eec"))
    )
    (comp (ref "SW56")
      (value "Switch_Key_Switch_MX1A-E1NW_eec")
      (footprint "SW_Cherry_MX_1.75u_PCB")
      (description "SWITCH PUSH SPST-NO 0.01A 12V")
      (fields
        (field (name "PART NUMBER") "MX1A-E1NW")
        (field (name "VOLTAGE") "12V")
        (field (name "MANUFACTURER") "Key Switch")
      )
      (libsource (lib "Switch_Key_Switch_MX1A-E1NW_eec") (part "Switch_Key_Switch_MX1A-E1NW_eec"))
    )
    (comp (ref "SW57")
      (value "Switch_Key_Switch_MX1A-E1NW_eec")
      (footprint "SW_Cherry_MX_1.00u_PCB")
      (description "SWITCH PUSH SPST-NO 0.01A 12V")
      (fields
        (field (name "PART NUMBER") "MX1A-E1NW")
        (field (name "VOLTAGE") "12V")
        (field (name "MANUFACTURER") "Key Switch")
      )
      (libsource (lib "Switch_Key_Switch_MX1A-E1NW_eec") (part "Switch_Key_Switch_MX1A-E1NW_eec"))
    )
    (comp (ref "SW58")
      (value "Switch_Key_Switch_MX1A-E1NW_eec")
      (footprint "SW_Cherry_MX_1.00u_PCB")
      (description "SWITCH PUSH SPST-NO 0.01A 12V")
      (fields
        (field (name "PART NUMBER") "MX1A-E1NW")
        (field (name "VOLTAGE") "12V")
        (field (name "MANUFACTURER") "Key Switch")
      )
      (libsource (lib "Switch_Key_Switch_MX1A-E1NW_eec") (part "Switch_Key_Switch_MX1A-E1NW_eec"))
    )
    (comp (ref "SW59")
      (value "Switch_Key_Switch_MX1A-E1NW_eec")
      (footprint "SW_Cherry_MX_1.50u_PCB")
      (description "SWITCH PUSH SPST-NO 0.01A 12V")
      (fields
        (field (name "PART NUMBER") "MX1A-E1NW")
        (field (name "VOLTAGE") "12V")
        (field (name "MANUFACTURER") "Key Switch")
      )
      (libsource (lib "Switch_Key_Switch_MX1A-E1NW_eec") (part "Switch_Key_Switch_MX1A-E1NW_eec"))
    )
    (comp (ref "SW60")
      (value "Switch_Key_Switch_MX1A-E1NW_eec")
      (footprint "SW_Cherry_MX_1.25u_PCB")
      (description "SWITCH PUSH SPST-NO 0.01A 12V")
      (fields
        (field (name "PART NUMBER") "MX1A-E1NW")
        (field (name "VOLTAGE") "12V")
        (field (name "MANUFACTURER") "Key Switch")
      )
      (libsource (lib "Switch_Key_Switch_MX1A-E1NW_eec") (part "Switch_Key_Switch_MX1A-E1NW_eec"))
    )
    (comp (ref "SW61")
      (value "Switch_Key_Switch_MX1A-E1NW_eec")
      (footprint "SW_Cherry_MX_1.50u_PCB")
      (description "SWITCH PUSH SPST-NO 0.01A 12V")
      (fields
        (field (name "PART NUMBER") "MX1A-E1NW")
        (field (name "VOLTAGE") "12V")
        (field (name "MANUFACTURER") "Key Switch")
      )
      (libsource (lib "Switch_Key_Switch_MX1A-E1NW_eec") (part "Switch_Key_Switch_MX1A-E1NW_eec"))
    )
    (comp (ref "SW62")
      (value "Switch_Key_Switch_MX1A-E1NW_eec")
      (footprint "SW_Cherry_MX_6.25u_PCB")
      (description "SWITCH PUSH SPST-NO 0.01A 12V")
      (fields
        (field (name "PART NUMBER") "MX1A-E1NW")
        (field (name "VOLTAGE") "12V")
        (field (name "MANUFACTURER") "Key Switch")
      )
      (libsource (lib "Switch_Key_Switch_MX1A-E1NW_eec") (part "Switch_Key_Switch_MX1A-E1NW_eec"))
    )
    (comp (ref "SW63")
      (value "Switch_Key_Switch_MX1A-E1NW_eec")
      (footprint "SW_Cherry_MX_1.25u_PCB")
      (description "SWITCH PUSH SPST-NO 0.01A 12V")
      (fields
        (field (name "PART NUMBER") "MX1A-E1NW")
        (field (name "VOLTAGE") "12V")
        (field (name "MANUFACTURER") "Key Switch")
      )
      (libsource (lib "Switch_Key_Switch_MX1A-E1NW_eec") (part "Switch_Key_Switch_MX1A-E1NW_eec"))
    )
    (comp (ref "SW64")
      (value "Switch_Key_Switch_MX1A-E1NW_eec")
      (footprint "SW_Cherry_MX_1.00u_PCB")
      (description "SWITCH PUSH SPST-NO 0.01A 12V")
      (fields
        (field (name "PART NUMBER") "MX1A-E1NW")
        (field (name "VOLTAGE") "12V")
        (field (name "MANUFACTURER") "Key Switch")
      )
      (libsource (lib "Switch_Key_Switch_MX1A-E1NW_eec") (part "Switch_Key_Switch_MX1A-E1NW_eec"))
    )
    (comp (ref "SW65")
      (value "Switch_Key_Switch_MX1A-E1NW_eec")
      (footprint "SW_Cherry_MX_1.00u_PCB")
      (description "SWITCH PUSH SPST-NO 0.01A 12V")
      (fields
        (field (name "PART NUMBER") "MX1A-E1NW")
        (field (name "VOLTAGE") "12V")
        (field (name "MANUFACTURER") "Key Switch")
      )
      (libsource (lib "Switch_Key_Switch_MX1A-E1NW_eec") (part "Switch_Key_Switch_MX1A-E1NW_eec"))
    )
    (comp (ref "SW66")
      (value "Switch_Key_Switch_MX1A-E1NW_eec")
      (footprint "SW_Cherry_MX_1.00u_PCB")
      (description "SWITCH PUSH SPST-NO 0.01A 12V")
      (fields
        (field (name "PART NUMBER") "MX1A-E1NW")
        (field (name "VOLTAGE") "12V")
        (field (name "MANUFACTURER") "Key Switch")
      )
      (libsource (lib "Switch_Key_Switch_MX1A-E1NW_eec") (part "Switch_Key_Switch_MX1A-E1NW_eec"))
    )
    (comp (ref "SW67")
      (value "Switch_Key_Switch_MX1A-E1NW_eec")
      (footprint "SW_Cherry_MX_1.00u_PCB")
      (description "SWITCH PUSH SPST-NO 0.01A 12V")
      (fields
        (field (name "PART NUMBER") "MX1A-E1NW")
        (field (name "VOLTAGE") "12V")
        (field (name "MANUFACTURER") "Key Switch")
      )
      (libsource (lib "Switch_Key_Switch_MX1A-E1NW_eec") (part "Switch_Key_Switch_MX1A-E1NW_eec"))
    )
  )
  (nets
    (net (code "1") (name "/col 0") (class "Default")
      (node (ref "SW1") (pin "2") (pinfunction "2_2") (pintype "passive"))
      (node (ref "SW16") (pin "2") (pinfunction "2_2") (pintype "passive"))
      (node (ref "SW31") (pin "2") (pinfunction "2_2") (pintype "passive"))
      (node (ref "SW45") (pin "2") (pinfunction "2_2") (pintype "passive"))
      (node (ref "SW59") (pin "2") (pinfunction "2_2") (pintype "passive"))
    )
    (net (code "2") (name "/col 1") (class "Default")
      (node (ref "SW17") (pin "2") (pinfunction "2_2") (pintype "passive"))
      (node (ref "SW2") (pin "2") (pinfunction "2_2") (pintype "passive"))
      (node (ref "SW32") (pin "2") (pinfunction "2_2") (pintype "passive"))
      (node (ref "SW46") (pin "2") (pinfunction "2_2") (pintype "passive"))
      (node (ref "SW60") (pin "2") (pinfunction "2_2") (pintype "passive"))
    )
    (net (code "3") (name "/col 2") (class "Default")
      (node (ref "SW18") (pin "2") (pinfunction "2_2") (pintype "passive"))
      (node (ref "SW3") (pin "2") (pinfunction "2_2") (pintype "passive"))
      (node (ref "SW33") (pin "2") (pinfunction "2_2") (pintype "passive"))
      (node (ref "SW47") (pin "2") (pinfunction "2_2") (pintype "passive"))
      (node (ref "SW61") (pin "2") (pinfunction "2_2") (pintype "passive"))
    )
    (net (code "4") (name "/col 3") (class "Default")
      (node (ref "SW19") (pin "2") (pinfunction "2_2") (pintype "passive"))
      (node (ref "SW34") (pin "2") (pinfunction "2_2") (pintype "passive"))
      (node (ref "SW4") (pin "2") (pinfunction "2_2") (pintype "passive"))
      (node (ref "SW48") (pin "2") (pinfunction "2_2") (pintype "passive"))
    )
    (net (code "5") (name "/col 4") (class "Default")
      (node (ref "SW20") (pin "2") (pinfunction "2_2") (pintype "passive"))
      (node (ref "SW35") (pin "2") (pinfunction "2_2") (pintype "passive"))
      (node (ref "SW49") (pin "2") (pinfunction "2_2") (pintype "passive"))
      (node (ref "SW5") (pin "2") (pinfunction "2_2") (pintype "passive"))
    )
    (net (code "6") (name "/col 5") (class "Default")
      (node (ref "SW21") (pin "2") (pinfunction "2_2") (pintype "passive"))
      (node (ref "SW36") (pin "2") (pinfunction "2_2") (pintype "passive"))
      (node (ref "SW50") (pin "2") (pinfunction "2_2") (pintype "passive"))
      (node (ref "SW6") (pin "2") (pinfunction "2_2") (pintype "passive"))
    )
    (net (code "7") (name "/col 6") (class "Default")
      (node (ref "SW22") (pin "2") (pinfunction "2_2") (pintype "passive"))
      (node (ref "SW37") (pin "2") (pinfunction "2_2") (pintype "passive"))
      (node (ref "SW51") (pin "2") (pinfunction "2_2") (pintype "passive"))
      (node (ref "SW62") (pin "2") (pinfunction "2_2") (pintype "passive"))
      (node (ref "SW7") (pin "2") (pinfunction "2_2") (pintype "passive"))
    )
    (net (code "8") (name "/col 7") (class "Default")
      (node (ref "SW23") (pin "2") (pinfunction "2_2") (pintype "passive"))
      (node (ref "SW38") (pin "2") (pinfunction "2_2") (pintype "passive"))
      (node (ref "SW52") (pin "2") (pinfunction "2_2") (pintype "passive"))
      (node (ref "SW8") (pin "2") (pinfunction "2_2") (pintype "passive"))
    )
    (net (code "9") (name "/col 8") (class "Default")
      (node (ref "SW24") (pin "2") (pinfunction "2_2") (pintype "passive"))
      (node (ref "SW39") (pin "2") (pinfunction "2_2") (pintype "passive"))
      (node (ref "SW53") (pin "2") (pinfunction "2_2") (pintype "passive"))
      (node (ref "SW9") (pin "2") (pinfunction "2_2") (pintype "passive"))
    )
    (net (code "10") (name "/col 9") (class "Default")
      (node (ref "SW10") (pin "2") (pinfunction "2_2") (pintype "passive"))
      (node (ref "SW25") (pin "2") (pinfunction "2_2") (pintype "passive"))
      (node (ref "SW40") (pin "2") (pinfunction "2_2") (pintype "passive"))
      (node (ref "SW54") (pin "2") (pinfunction "2_2") (pintype "passive"))
    )
    (net (code "11") (name "/col 10") (class "Default")
      (node (ref "SW11") (pin "2") (pinfunction "2_2") (pintype "passive"))
      (node (ref "SW26") (pin "2") (pinfunction "2_2") (pintype "passive"))
      (node (ref "SW41") (pin "2") (pinfunction "2_2") (pintype "passive"))
      (node (ref "SW55") (pin "2") (pinfunction "2_2") (pintype "passive"))
      (node (ref "SW63") (pin "2") (pinfunction "2_2") (pintype "passive"))
    )
    (net (code "12") (name "/col 11") (class "Default")
      (node (ref "SW12") (pin "2") (pinfunction "2_2") (pintype "passive"))
      (node (ref "SW27") (pin "2") (pinfunction "2_2") (pintype "passive"))
      (node (ref "SW42") (pin "2") (pinfunction "2_2") (pintype "passive"))
      (node (ref "SW64") (pin "2") (pinfunction "2_2") (pintype "passive"))
    )
    (net (code "13") (name "/col 12") (class "Default")
      (node (ref "SW13") (pin "2") (pinfunction "2_2") (pintype "passive"))
      (node (ref "SW28") (pin "2") (pinfunction "2_2") (pintype "passive"))
      (node (ref "SW56") (pin "2") (pinfunction "2_2") (pintype "passive"))
      (node (ref "SW65") (pin "2") (pinfunction "2_2") (pintype "passive"))
    )
    (net (code "14") (name "/col 13") (class "Default")
      (node (ref "SW14") (pin "2") (pinfunction "2_2") (pintype "passive"))
      (node (ref "SW29") (pin "2") (pinfunction "2_2") (pintype "passive"))
      (node (ref "SW43") (pin "2") (pinfunction "2_2") (pintype "passive"))
      (node (ref "SW57") (pin "2") (pinfunction "2_2") (pintype "passive"))
      (node (ref "SW66") (pin "2") (pinfunction "2_2") (pintype "passive"))
    )
    (net (code "15") (name "/col 14") (class "Default")
      (node (ref "SW15") (pin "2") (pinfunction "2_2") (pintype "passive"))
      (node (ref "SW30") (pin "2") (pinfunction "2_2") (pintype "passive"))
      (node (ref "SW44") (pin "2") (pinfunction "2_2") (pintype "passive"))
      (node (ref "SW58") (pin "2") (pinfunction "2_2") (pintype "passive"))
      (node (ref "SW67") (pin "2") (pinfunction "2_2") (pintype "passive"))
    )
    (net (code "16") (name "/row 0") (class "Default")
      (node (ref "D1") (pin "1") (pinfunction "C_1") (pintype "passive"))
      (node (ref "D10") (pin "1") (pinfunction "C_1") (pintype "passive"))
      (node (ref "D11") (pin "1") (pinfunction "C_1") (pintype "passive"))
      (node (ref "D12") (pin "1") (pinfunction "C_1") (pintype "passive"))
      (node (ref "D13") (pin "1") (pinfunction "C_1") (pintype "passive"))
      (node (ref "D14") (pin "1") (pinfunction "C_1") (pintype "passive"))
      (node (ref "D15") (pin "1") (pinfunction "C_1") (pintype "passive"))
      (node (ref "D2") (pin "1") (pinfunction "C_1") (pintype "passive"))
      (node (ref "D3") (pin "1") (pinfunction "C_1") (pintype "passive"))
      (node (ref "D4") (pin "1") (pinfunction "C_1") (pintype "passive"))
      (node (ref "D5") (pin "1") (pinfunction "C_1") (pintype "passive"))
      (node (ref "D6") (pin "1") (pinfunction "C_1") (pintype "passive"))
      (node (ref "D7") (pin "1") (pinfunction "C_1") (pintype "passive"))
      (node (ref "D8") (pin "1") (pinfunction "C_1") (pintype "passive"))
      (node (ref "D9") (pin "1") (pinfunction "C_1") (pintype "passive"))
    )
    (net (code "17") (name "/row 1") (class "Default")
      (node (ref "D16") (pin "1") (pinfunction "C_1") (pintype "passive"))
      (node (ref "D17") (pin "1") (pinfunction "C_1") (pintype "passive"))
      (node (ref "D18") (pin "1") (pinfunction "C_1") (pintype "passive"))
      (node (ref "D19") (pin "1") (pinfunction "C_1") (pintype "passive"))
      (node (ref "D20") (pin "1") (pinfunction "C_1") (pintype "passive"))
      (node (ref "D21") (pin "1") (pinfunction "C_1") (pintype "passive"))
      (node (ref "D22") (pin "1") (pinfunction "C_1") (pintype "passive"))
      (node (ref "D23") (pin "1") (pinfunction "C_1") (pintype "passive"))
      (node (ref "D24") (pin "1") (pinfunction "C_1") (pintype "passive"))
      (node (ref "D25") (pin "1") (pinfunction "C_1") (pintype "passive"))
      (node (ref "D26") (pin "1") (pinfunction "C_1") (pintype "passive"))
      (node (ref "D27") (pin "1") (pinfunction "C_1") (pintype "passive"))
      (node (ref "D28") (pin "1") (pinfunction "C_1") (pintype "passive"))
      (node (ref "D29") (pin "1") (pinfunction "C_1") (pintype "passive"))
      (node (ref "D30") (pin "1") (pinfunction "C_1") (pintype "passive"))
    )
    (net (code "18") (name "/row 2") (class "Default")
      (node (ref "D31") (pin "1") (pinfunction "C_1") (pintype "passive"))
      (node (ref "D32") (pin "1") (pinfunction "C_1") (pintype "passive"))
      (node (ref "D33") (pin "1") (pinfunction "C_1") (pintype "passive"))
      (node (ref "D34") (pin "1") (pinfunction "C_1") (pintype "passive"))
      (node (ref "D35") (pin "1") (pinfunction "C_1") (pintype "passive"))
      (node (ref "D36") (pin "1") (pinfunction "C_1") (pintype "passive"))
      (node (ref "D37") (pin "1") (pinfunction "C_1") (pintype "passive"))
      (node (ref "D38") (pin "1") (pinfunction "C_1") (pintype "passive"))
      (node (ref "D39") (pin "1") (pinfunction "C_1") (pintype "passive"))
      (node (ref "D40") (pin "1") (pinfunction "C_1") (pintype "passive"))
      (node (ref "D41") (pin "1") (pinfunction "C_1") (pintype "passive"))
      (node (ref "D42") (pin "1") (pinfunction "C_1") (pintype "passive"))
      (node (ref "D43") (pin "1") (pinfunction "C_1") (pintype "passive"))
      (node (ref "D44") (pin "1") (pinfunction "C_1") (pintype "passive"))
    )
    (net (code "19") (name "/row 3") (class "Default")
      (node (ref "D45") (pin "1") (pinfunction "C_1") (pintype "passive"))
      (node (ref "D46") (pin "1") (pinfunction "C_1") (pintype "passive"))
      (node (ref "D47") (pin "1") (pinfunction "C_1") (pintype "passive"))
      (node (ref "D48") (pin "1") (pinfunction "C_1") (pintype "passive"))
      (node (ref "D49") (pin "1") (pinfunction "C_1") (pintype "passive"))
      (node (ref "D50") (pin "1") (pinfunction "C_1") (pintype "passive"))
      (node (ref "D51") (pin "1") (pinfunction "C_1") (pintype "passive"))
      (node (ref "D52") (pin "1") (pinfunction "C_1") (pintype "passive"))
      (node (ref "D53") (pin "1") (pinfunction "C_1") (pintype "passive"))
      (node (ref "D54") (pin "1") (pinfunction "C_1") (pintype "passive"))
      (node (ref "D55") (pin "1") (pinfunction "C_1") (pintype "passive"))
      (node (ref "D56") (pin "1") (pinfunction "C_1") (pintype "passive"))
      (node (ref "D57") (pin "1") (pinfunction "C_1") (pintype "passive"))
      (node (ref "D58") (pin "1") (pinfunction "C_1") (pintype "passive"))
    )
    (net (code "20") (name "/row 4") (class "Default")
      (node (ref "D59") (pin "1") (pinfunction "C_1") (pintype "passive"))
      (node (ref "D60") (pin "1") (pinfunction "C_1") (pintype "passive"))
      (node (ref "D61") (pin "1") (pinfunction "C_1") (pintype "passive"))
      (node (ref "D62") (pin "1") (pinfunction "C_1") (pintype "passive"))
      (node (ref "D63") (pin "1") (pinfunction "C_1") (pintype "passive"))
      (node (ref "D64") (pin "1") (pinfunction "C_1") (pintype "passive"))
      (node (ref "D65") (pin "1") (pinfunction "C_1") (pintype "passive"))
      (node (ref "D66") (pin "1") (pinfunction "C_1") (pintype "passive"))
      (node (ref "D67") (pin "1") (pinfunction "C_1") (pintype "passive"))
    )
    (net (code "21") (name "Net-(D1-A)") (class "Default")
      (node (ref "D1") (pin "2") (pinfunction "A_2") (pintype "passive"))
      (node (ref "SW1") (pin "1") (pinfunction "1_1") (pintype "passive"))
    )
    (net (code "22") (name "Net-(D2-A)") (class "Default")
      (node (ref "D2") (pin "2") (pinfunction "A_2") (pintype "passive"))
      (node (ref "SW2") (pin "1") (pinfunction "1_1") (pintype "passive"))
    )
    (net (code "23") (name "Net-(D3-A)") (class "Default")
      (node (ref "D3") (pin "2") (pinfunction "A_2") (pintype "passive"))
      (node (ref "SW3") (pin "1") (pinfunction "1_1") (pintype "passive"))
    )
    (net (code "24") (name "Net-(D4-A)") (class "Default")
      (node (ref "D4") (pin "2") (pinfunction "A_2") (pintype "passive"))
      (node (ref "SW4") (pin "1") (pinfunction "1_1") (pintype "passive"))
    )
    (net (code "25") (name "Net-(D5-A)") (class "Default")
      (node (ref "D5") (pin "2") (pinfunction "A_2") (pintype "passive"))
      (node (ref "SW5") (pin "1") (pinfunction "1_1") (pintype "passive"))
    )
    (net (code "26") (name "Net-(D6-A)") (class "Default")
      (node (ref "D6") (pin "2") (pinfunction "A_2") (pintype "passive"))
      (node (ref "SW6") (pin "1") (pinfunction "1_1") (pintype "passive"))
    )
    (net (code "27") (name "Net-(D7-A)") (class "Default")
      (node (ref "D7") (pin "2") (pinfunction "A_2") (pintype "passive"))
      (node (ref "SW7") (pin "1") (pinfunction "1_1") (pintype "passive"))
    )
    (net (code "28") (name "Net-(D8-A)") (class "Default")
      (node (ref "D8") (pin "2") (pinfunction "A_2") (pintype "passive"))
      (node (ref "SW8") (pin "1") (pinfunction "1_1") (pintype "passive"))
    )
    (net (code "29") (name "Net-(D9-A)") (class "Default")
      (node (ref "D9") (pin "2") (pinfunction "A_2") (pintype "passive"))
      (node (ref "SW9") (pin "1") (pinfunction "1_1") (pintype "passive"))
    )
    (net (code "30") (name "Net-(D10-A)") (class "Default")
      (node (ref "D10") (pin "2") (pinfunction "A_2") (pintype "passive"))
      (node (ref "SW10") (pin "1") (pinfunction "1_1") (pintype "passive"))
    )
    (net (code "31") (name "Net-(D11-A)") (class "Default")
      (node (ref "D11") (pin "2") (pinfunction "A_2") (pintype "passive"))
      (node (ref "SW11") (pin "1") (pinfunction "1_1") (pintype "passive"))
    )
    (net (code "32") (name "Net-(D12-A)") (class "Default")
      (node (ref "D12") (pin "2") (pinfunction "A_2") (pintype "passive"))
      (node (ref "SW12") (pin "1") (pinfunction "1_1") (pintype "passive"))
    )
    (net (code "33") (name "Net-(D13-A)") (class "Default")
      (node (ref "D13") (pin "2") (pinfunction "A_2") (pintype "passive"))
      (node (ref "SW13") (pin "1") (pinfunction "1_1") (pintype "passive"))
    )
    (net (code "34") (name "Net-(D14-A)") (class "Default")
      (node (ref "D14") (pin "2") (pinfunction "A_2") (pintype "passive"))
      (node (ref "SW14") (pin "1") (pinfunction "1_1") (pintype "passive"))
    )
    (net (code "35") (name "Net-(D15-A)") (class "Default")
      (node (ref "D15") (pin "2") (pinfunction "A_2") (pintype "passive"))
      (node (ref "SW15") (pin "1") (pinfunction "1_1") (pintype "passive"))
    )
    (net (code "36") (name "Net-(D16-A)") (class "Default")
      (node (ref "D16") (pin "2") (pinfunction "A_2") (pintype "passive"))
      (node (ref "SW16") (pin "1") (pinfunction "1_1") (pintype "passive"))
    )
    (net (code "37") (name "Net-(D17-A)") (class "Default")
      (node (ref "D17") (pin "2") (pinfunction "A_2") (pintype "passive"))
      (node (ref "SW17") (pin "1") (pinfunction "1_1") (pintype "passive"))
    )
    (net (code "38") (name "Net-(D18-A)") (class "Default")
      (node (ref "D18") (pin "2") (pinfunction "A_2") (pintype "passive"))
      (node (ref "SW18") (pin "1") (pinfunction "1_1") (pintype "passive"))
    )
    (net (code "39") (name "Net-(D19-A)") (class "Default")
      (node (ref "D19") (pin "2") (pinfunction "A_2") (pintype "passive"))
      (node (ref "SW19") (pin "1") (pinfunction "1_1") (pintype "passive"))
    )
    (net (code "40") (name "Net-(D20-A)") (class "Default")
      (node (ref "D20") (pin "2") (pinfunction "A_2") (pintype "passive"))
      (node (ref "SW20") (pin "1") (pinfunction "1_1") (pintype "passive"))
    )
    (net (code "41") (name "Net-(D21-A)") (class "Default")
      (node (ref "D21") (pin "2") (pinfunction "A_2") (pintype "passive"))
      (node (ref "SW21") (pin "1") (pinfunction "1_1") (pintype "passive"))
    )
    (net (code "42") (name "Net-(D22-A)") (class "Default")
      (node (ref "D22") (pin "2") (pinfunction "A_2") (pintype "passive"))
      (node (ref "SW22") (pin "1") (pinfunction "1_1") (pintype "passive"))
    )
    (net (code "43") (name "Net-(D23-A)") (class "Default")
      (node (ref "D23") (pin "2") (pinfunction "A_2") (pintype "passive"))
      (node (ref "SW23") (pin "1") (pinfunction "1_1") (pintype "passive"))
    )
    (net (code "44") (name "Net-(D24-A)") (class "Default")
      (node (ref "D24") (pin "2") (pinfunction "A_2") (pintype "passive"))
      (node (ref "SW24") (pin "1") (pinfunction "1_1") (pintype "passive"))
    )
    (net (code "45") (name "Net-(D25-A)") (class "Default")
      (node (ref "D25") (pin "2") (pinfunction "A_2") (pintype "passive"))
      (node (ref "SW25") (pin "1") (pinfunction "1_1") (pintype "passive"))
    )
    (net (code "46") (name "Net-(D26-A)") (class "Default")
      (node (ref "D26") (pin "2") (pinfunction "A_2") (pintype "passive"))
      (node (ref "SW26") (pin "1") (pinfunction "1_1") (pintype "passive"))
    )
    (net (code "47") (name "Net-(D27-A)") (class "Default")
      (node (ref "D27") (pin "2") (pinfunction "A_2") (pintype "passive"))
      (node (ref "SW27") (pin "1") (pinfunction "1_1") (pintype "passive"))
    )
    (net (code "48") (name "Net-(D28-A)") (class "Default")
      (node (ref "D28") (pin "2") (pinfunction "A_2") (pintype "passive"))
      (node (ref "SW28") (pin "1") (pinfunction "1_1") (pintype "passive"))
    )
    (net (code "49") (name "Net-(D29-A)") (class "Default")
      (node (ref "D29") (pin "2") (pinfunction "A_2") (pintype "passive"))
      (node (ref "SW29") (pin "1") (pinfunction "1_1") (pintype "passive"))
    )
    (net (code "50") (name "Net-(D30-A)") (class "Default")
      (node (ref "D30") (pin "2") (pinfunction "A_2") (pintype "passive"))
      (node (ref "SW30") (pin "1") (pinfunction "1_1") (pintype "passive"))
    )
    (net (code "51") (name "Net-(D31-A)") (class "Default")
      (node (ref "D31") (pin "2") (pinfunction "A_2") (pintype "passive"))
      (node (ref "SW31") (pin "1") (pinfunction "1_1") (pintype "passive"))
    )
    (net (code "52") (name "Net-(D32-A)") (class "Default")
      (node (ref "D32") (pin "2") (pinfunction "A_2") (pintype "passive"))
      (node (ref "SW32") (pin "1") (pinfunction "1_1") (pintype "passive"))
    )
    (net (code "53") (name "Net-(D33-A)") (class "Default")
      (node (ref "D33") (pin "2") (pinfunction "A_2") (pintype "passive"))
      (node (ref "SW33") (pin "1") (pinfunction "1_1") (pintype "passive"))
    )
    (net (code "54") (name "Net-(D34-A)") (class "Default")
      (node (ref "D34") (pin "2") (pinfunction "A_2") (pintype "passive"))
      (node (ref "SW34") (pin "1") (pinfunction "1_1") (pintype "passive"))
    )
    (net (code "55") (name "Net-(D35-A)") (class "Default")
      (node (ref "D35") (pin "2") (pinfunction "A_2") (pintype "passive"))
      (node (ref "SW35") (pin "1") (pinfunction "1_1") (pintype "passive"))
    )
    (net (code "56") (name "Net-(D36-A)") (class "Default")
      (node (ref "D36") (pin "2") (pinfunction "A_2") (pintype "passive"))
      (node (ref "SW36") (pin "1") (pinfunction "1_1") (pintype "passive"))
    )
    (net (code "57") (name "Net-(D37-A)") (class "Default")
      (node (ref "D37") (pin "2") (pinfunction "A_2") (pintype "passive"))
      (node (ref "SW37") (pin "1") (pinfunction "1_1") (pintype "passive"))
    )
    (net (code "58") (name "Net-(D38-A)") (class "Default")
      (node (ref "D38") (pin "2") (pinfunction "A_2") (pintype "passive"))
      (node (ref "SW38") (pin "1") (pinfunction "1_1") (pintype "passive"))
    )
    (net (code "59") (name "Net-(D39-A)") (class "Default")
      (node (ref "D39") (pin "2") (pinfunction "A_2") (pintype "passive"))
      (node (ref "SW39") (pin "1") (pinfunction "1_1") (pintype "passive"))
    )
    (net (code "60") (name "Net-(D40-A)") (class "Default")
      (node (ref "D40") (pin "2") (pinfunction "A_2") (pintype "passive"))
      (node (ref "SW40") (pin "1") (pinfunction "1_1") (pintype "passive"))
    )
    (net (code "61") (name "Net-(D41-A)") (class "Default")
      (node (ref "D41") (pin "2") (pinfunction "A_2") (pintype "passive"))
      (node (ref "SW41") (pin "1") (pinfunction "1_1") (pintype "passive"))
    )
    (net (code "62") (name "Net-(D42-A)") (class "Default")
      (node (ref "D42") (pin "2") (pinfunction "A_2") (pintype "passive"))
      (node (ref "SW42") (pin "1") (pinfunction "1_1") (pintype "passive"))
    )
    (net (code "63") (name "Net-(D43-A)") (class "Default")
      (node (ref "D43") (pin "2") (pinfunction "A_2") (pintype "passive"))
      (node (ref "SW43") (pin "1") (pinfunction "1_1") (pintype "passive"))
    )
    (net (code "64") (name "Net-(D44-A)") (class "Default")
      (node (ref "D44") (pin "2") (pinfunction "A_2") (pintype "passive"))
      (node (ref "SW44") (pin "1") (pinfunction "1_1") (pintype "passive"))
    )
    (net (code "65") (name "Net-(D45-A)") (class "Default")
      (node (ref "D45") (pin "2") (pinfunction "A_2") (pintype "passive"))
      (node (ref "SW45") (pin "1") (pinfunction "1_1") (pintype "passive"))
    )
    (net (code "66") (name "Net-(D46-A)") (class "Default")
      (node (ref "D46") (pin "2") (pinfunction "A_2") (pintype "passive"))
      (node (ref "SW46") (pin "1") (pinfunction "1_1") (pintype "passive"))
    )
    (net (code "67") (name "Net-(D47-A)") (class "Default")
      (node (ref "D47") (pin "2") (pinfunction "A_2") (pintype "passive"))
      (node (ref "SW47") (pin "1") (pinfunction "1_1") (pintype "passive"))
    )
    (net (code "68") (name "Net-(D48-A)") (class "Default")
      (node (ref "D48") (pin "2") (pinfunction "A_2") (pintype "passive"))
      (node (ref "SW48") (pin "1") (pinfunction "1_1") (pintype "passive"))
    )
    (net (code "69") (name "Net-(D49-A)") (class "Default")
      (node (ref "D49") (pin "2") (pinfunction "A_2") (pintype "passive"))
      (node (ref "SW49") (pin "1") (pinfunction "1_1") (pintype "passive"))
    )
    (net (code "70") (name "Net-(D50-A)") (class "Default")
      (node (ref "D50") (pin "2") (pinfunction "A_2") (pintype "passive"))
      (node (ref "SW50") (pin "1") (pinfunction "1_1") (pintype "passive"))
    )
    (net (code "71") (name "Net-(D51-A)") (class "Default")
      (node (ref "D51") (pin "2") (pinfunction "A_2") (pintype "passive"))
      (node (ref "SW51") (pin "1") (pinfunction "1_1") (pintype "passive"))
    )
    (net (code "72") (name "Net-(D52-A)") (class "Default")
      (node (ref "D52") (pin "2") (pinfunction "A_2") (pintype "passive"))
      (node (ref "SW52") (pin "1") (pinfunction "1_1") (pintype "passive"))
    )
    (net (code "73") (name "Net-(D53-A)") (class "Default")
      (node (ref "D53") (pin "2") (pinfunction "A_2") (pintype "passive"))
      (node (ref "SW53") (pin "1") (pinfunction "1_1") (pintype "passive"))
    )
    (net (code "74") (name "Net-(D54-A)") (class "Default")
      (node (ref "D54") (pin "2") (pinfunction "A_2") (pintype "passive"))
      (node (ref "SW54") (pin "1") (pinfunction "1_1") (pintype "passive"))
    )
    (net (code "75") (name "Net-(D55-A)") (class "Default")
      (node (ref "D55") (pin "2") (pinfunction "A_2") (pintype "passive"))
      (node (ref "SW55") (pin "1") (pinfunction "1_1") (pintype "passive"))
    )
    (net (code "76") (name "Net-(D56-A)") (class "Default")
      (node (ref "D56") (pin "2") (pinfunction "A_2") (pintype "passive"))
      (node (ref "SW56") (pin "1") (pinfunction "1_1") (pintype "passive"))
    )
    (net (code "77") (name "Net-(D57-A)") (class "Default")
      (node (ref "D57") (pin "2") (pinfunction "A_2") (pintype "passive"))
      (node (ref "SW57") (pin "1") (pinfunction "1_1") (pintype "passive"))
    )
    (net (code "78") (name "Net-(D58-A)") (class "Default")
      (node (ref "D58") (pin "2") (pinfunction "A_2") (pintype "passive"))
      (node (ref "SW58") (pin "1") (pinfunction "1_1") (pintype "passive"))
    )
    (net (code "79") (name "Net-(D59-A)") (class "Default")
      (node (ref "D59") (pin "2") (pinfunction "A_2") (pintype "passive"))
      (node (ref "SW59") (pin "1") (pinfunction "1_1") (pintype "passive"))
    )
    (net (code "80") (name "Net-(D60-A)") (class "Default")
      (node (ref "D60") (pin "2") (pinfunction "A_2") (pintype "passive"))
      (node (ref "SW60") (pin "1") (pinfunction "1_1") (pintype "passive"))
    )
    (net (code "81") (name "Net-(D61-A)") (class "Default")
      (node (ref "D61") (pin "2") (pinfunction "A_2") (pintype "passive"))
      (node (ref "SW61") (pin "1") (pinfunction "1_1") (pintype "passive"))
    )
    (net (code "82") (name "Net-(D62-A)") (class "Default")
      (node (ref "D62") (pin "2") (pinfunction "A_2") (pintype "passive"))
      (node (ref "SW62") (pin "1") (pinfunction "1_1") (pintype "passive"))
    )
    (net (code "83") (name "Net-(D63-A)") (class "Default")
      (node (ref "D63") (pin "2") (pinfunction "A_2") (pintype "passive"))
      (node (ref "SW63") (pin "1") (pinfunction "1_1") (pintype "passive"))
    )
    (net (code "84") (name "Net-(D64-A)") (class "Default")
      (node (ref "D64") (pin "2") (pinfunction "A_2") (pintype "passive"))
      (node (ref "SW64") (pin "1") (pinfunction "1_1") (pintype "passive"))
    )
    (net (code "85") (name "Net-(D65-A)") (class "Default")
      (node (ref "D65") (pin "2") (pinfunction "A_2") (pintype "passive"))
      (node (ref "SW65") (pin "1") (pinfunction "1_1") (pintype "passive"))
    )
    (net (code "86") (name "Net-(D66-A)") (class "Default")
      (node (ref "D66") (pin "2") (pinfunction "A_2") (pintype "passive"))
      (node (ref "SW66") (pin "1") (pinfunction "1_1") (pintype "passive"))
    )
    (net (code "87") (name "Net-(D67-A)") (class "Default")
      (node (ref "D67") (pin "2") (pinfunction "A_2") (pintype "passive"))
      (node (ref "SW67") (pin "1") (pinfunction "1_1") (pintype "passive"))
    )
  )
)
